# CC-S11-V00-Power.net
KiCad netlist of a schematic drawn in Altium Designer
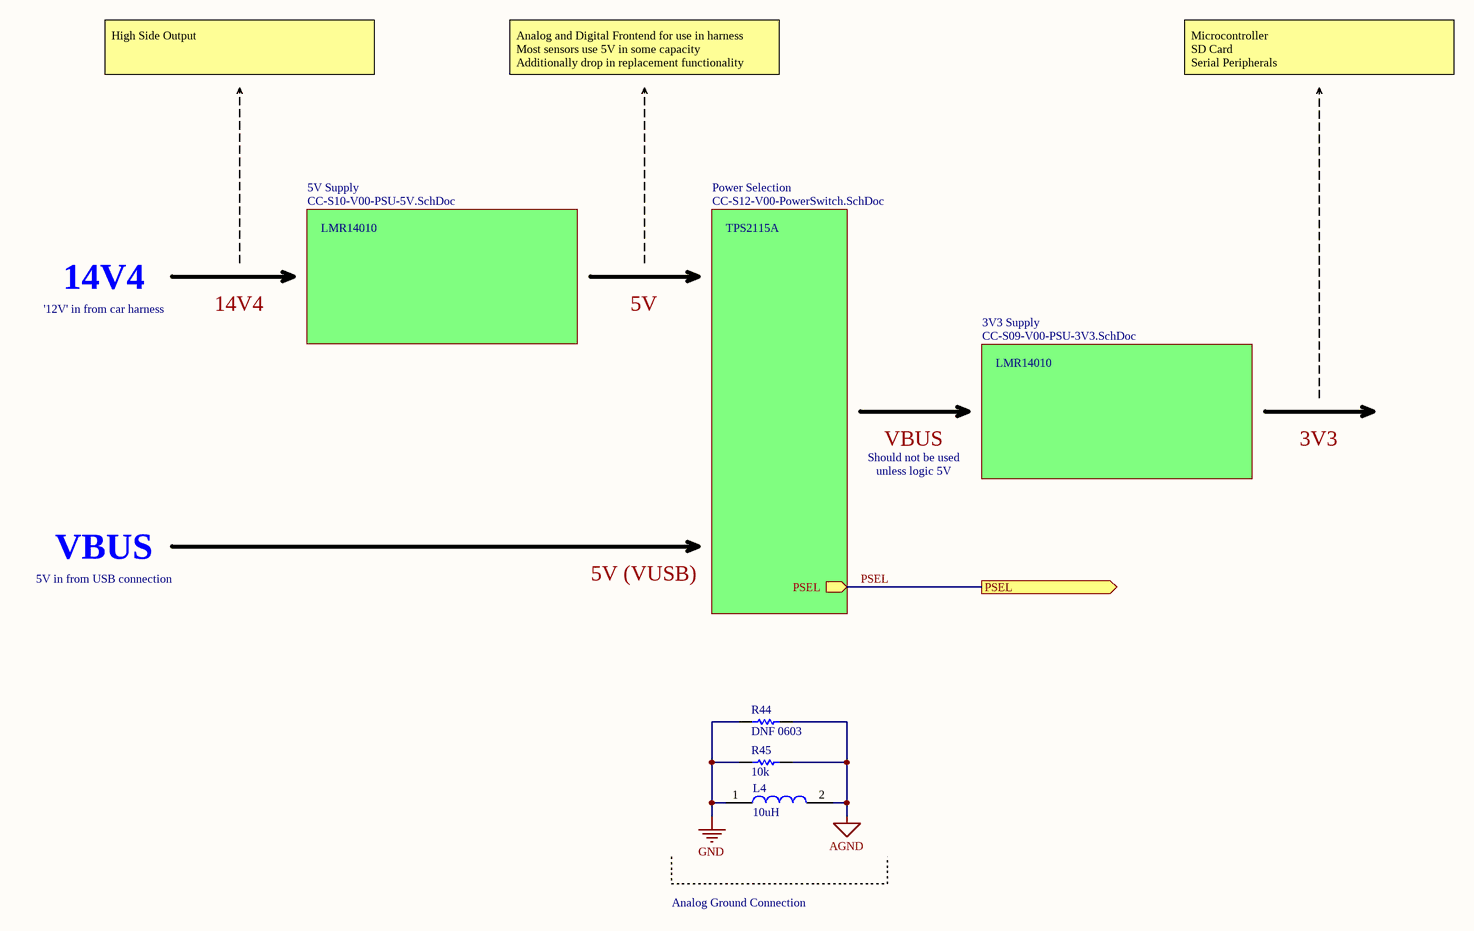
[diagram p0: CC-S11-V00-Power.SchDoc]

(export (version "E")
  (design (tool "Eeschema 10.0.6"))
  (components
    (comp (ref "L4")
      (value "10uH")
      (footprint "Inductor_0603")
      (description "10uH, 10%, 0603")
      (libsource (lib "QUTMS_InductorLibrary") (part "10uH, 10%, 0603"))
    )
    (comp (ref "R44")
      (value "DNF 0603")
      (footprint "Res_ThinFilm_0603")
      (description "Resistor, SMD, DNF, 0.1W, 0603")
      (libsource (lib "StandardResistors") (part "DNF 0603"))
    )
    (comp (ref "R45")
      (value "10k")
      (footprint "Res_ThinFilm_0603")
      (description "Resistor, SMD, 10k, 0.1W, 5%, 0603")
      (libsource (lib "StandardResistors") (part "10k 5% 0603"))
    )
  )
  (nets
    (net (code "2") (name "AGND") (class "Default")
      (node (ref "L4") (pin "2") (pinfunction "2_2") (pintype "passive"))
      (node (ref "R44") (pin "2") (pinfunction "2_2") (pintype "passive"))
      (node (ref "R45") (pin "2") (pinfunction "2_2") (pintype "passive"))
    )
    (net (code "3") (name "GND") (class "Default")
      (node (ref "L4") (pin "1") (pinfunction "1_1") (pintype "passive"))
      (node (ref "R44") (pin "1") (pinfunction "1_1") (pintype "passive"))
      (node (ref "R45") (pin "1") (pinfunction "1_1") (pintype "passive"))
    )
  )
)
